# light-meter-A.net
KiCad netlist of a schematic drawn in EAGLE
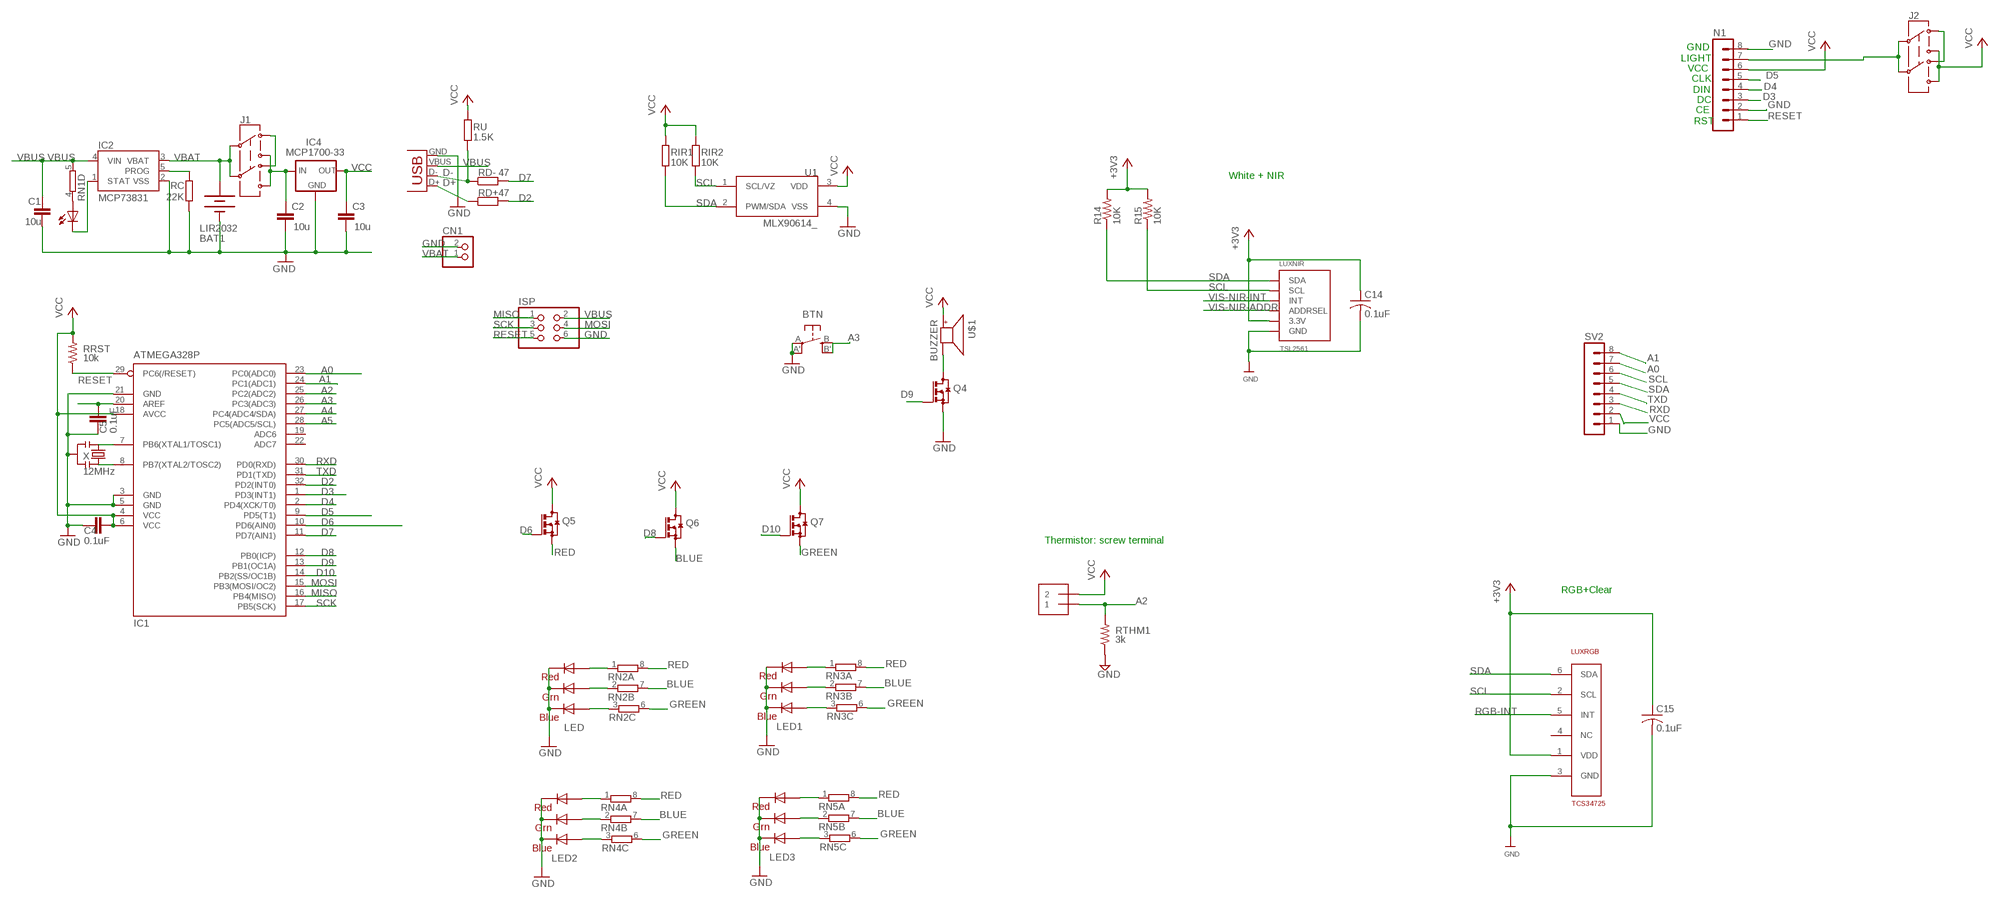
[diagram p0: schematic, sheet 1]

(export (version "E")
  (design (tool "Eeschema 10.0.6"))
  (components
    (comp (ref "BAT1")
      (value "LIR2032")
      (footprint "eagle-import:BATTCOM_20MM_PTH_SMT")
      (libsource (lib "eagle-import") (part "BATTERYBATTCOM_20MM_PTH_SMT"))
    )
    (comp (ref "BTN")
      (value "EVQQ2")
      (footprint "eagle-import:EVQ-Q2")
      (libsource (lib "eagle-import") (part "EVQQ2"))
    )
    (comp (ref "C1")
      (value "10u")
      (footprint "eagle-import:C0805")
      (libsource (lib "eagle-import") (part "resistor_C-EUC0805"))
    )
    (comp (ref "C2")
      (value "10u")
      (footprint "eagle-import:C0805")
      (libsource (lib "eagle-import") (part "resistor_C-EUC0805"))
    )
    (comp (ref "C3")
      (value "10u")
      (footprint "eagle-import:C0805")
      (libsource (lib "eagle-import") (part "resistor_C-EUC0805"))
    )
    (comp (ref "C4")
      (value "0.1uF")
      (footprint "eagle-import:C0805")
      (libsource (lib "eagle-import") (part "C-EUC0805"))
    )
    (comp (ref "C5")
      (value "0.1uF")
      (footprint "eagle-import:C0805")
      (libsource (lib "eagle-import") (part "C-EUC0805"))
    )
    (comp (ref "C14")
      (value "0.1uF")
      (footprint "eagle-import:C0805")
      (libsource (lib "eagle-import") (part "C-USC0805"))
    )
    (comp (ref "C15")
      (value "0.1uF")
      (footprint "eagle-import:C0805")
      (libsource (lib "eagle-import") (part "C-USC0805"))
    )
    (comp (ref "CHG")
      (value "0805")
      (footprint "eagle-import:CHIPLED_0805")
      (libsource (lib "eagle-import") (part "LEDCHIPLED_0805"))
    )
    (comp (ref "CN1")
      (value "JST_2PIN-SMT-RA")
      (footprint "eagle-import:JST-PH-2-SMT-RA")
      (libsource (lib "eagle-import") (part "JST_2PIN-SMT-RA"))
    )
    (comp (ref "IC1")
      (value "ATMEGA328P")
      (footprint "eagle-import:TQFP32-08")
      (fields (field (name "MPN") "ATMEGA8-16AU"))
      (libsource (lib "eagle-import") (part "MEGA8-AI"))
    )
    (comp (ref "IC2")
      (value "MCP73831")
      (footprint "eagle-import:SOT23-5")
      (libsource (lib "eagle-import") (part "MCP73831"))
    )
    (comp (ref "IC4")
      (value "MCP1700-33")
      (footprint "eagle-import:SOT23")
      (libsource (lib "eagle-import") (part "MCP1700SOT233"))
    )
    (comp (ref "ISP")
      (value "PINHD-2X3")
      (footprint "eagle-import:2X03")
      (libsource (lib "eagle-import") (part "PINHD-2X3"))
    )
    (comp (ref "J1")
      (value "AYZ0202")
      (footprint "eagle-import:AYZ0202")
      (libsource (lib "eagle-import") (part "AYZ0202"))
    )
    (comp (ref "J2")
      (value "AYZ0202")
      (footprint "eagle-import:AYZ0202")
      (libsource (lib "eagle-import") (part "AYZ0202"))
    )
    (comp (ref "LED")
      (value "RGBLED5050")
      (footprint "eagle-import:RGBLED5050")
      (libsource (lib "eagle-import") (part "RGBLED5050"))
    )
    (comp (ref "LED1")
      (value "RGBLED5050")
      (footprint "eagle-import:RGBLED5050")
      (libsource (lib "eagle-import") (part "RGBLED5050"))
    )
    (comp (ref "LED2")
      (value "RGBLED5050")
      (footprint "eagle-import:RGBLED5050")
      (libsource (lib "eagle-import") (part "RGBLED5050"))
    )
    (comp (ref "LED3")
      (value "RGBLED5050")
      (footprint "eagle-import:RGBLED5050")
      (libsource (lib "eagle-import") (part "RGBLED5050"))
    )
    (comp (ref "LUXNIR")
      (value "TSL2561")
      (footprint "eagle-import:TSL2561_FN@1")
      (libsource (lib "eagle-import") (part "TSL2561"))
    )
    (comp (ref "LUXRGB")
      (value "TCS34725")
      (footprint "eagle-import:DFN-6")
      (libsource (lib "eagle-import") (part "TCS34725"))
    )
    (comp (ref "N1")
      (value "MA08-1")
      (footprint "eagle-import:MA08-1")
      (libsource (lib "eagle-import") (part "MA08-1"))
    )
    (comp (ref "Q4")
      (value "BSS123")
      (footprint "eagle-import:SOT23")
      (libsource (lib "eagle-import") (part "BSS123"))
    )
    (comp (ref "Q5")
      (value "BSS123")
      (footprint "eagle-import:SOT23")
      (libsource (lib "eagle-import") (part "BSS123"))
    )
    (comp (ref "Q6")
      (value "BSS123")
      (footprint "eagle-import:SOT23")
      (libsource (lib "eagle-import") (part "BSS123"))
    )
    (comp (ref "Q7")
      (value "BSS123")
      (footprint "eagle-import:SOT23")
      (libsource (lib "eagle-import") (part "BSS123"))
    )
    (comp (ref "R14")
      (value "10K")
      (footprint "eagle-import:R0805")
      (libsource (lib "eagle-import") (part "R-US_R0805"))
    )
    (comp (ref "R15")
      (value "10K")
      (footprint "eagle-import:R0805")
      (libsource (lib "eagle-import") (part "R-US_R0805"))
    )
    (comp (ref "RC")
      (value "22K")
      (footprint "eagle-import:R0805")
      (libsource (lib "eagle-import") (part "R-EU_R0805"))
    )
    (comp (ref "RD+")
      (value "47")
      (footprint "eagle-import:R0805")
      (libsource (lib "eagle-import") (part "R-EU_R0805"))
    )
    (comp (ref "RD-")
      (value "47")
      (footprint "eagle-import:R0805")
      (libsource (lib "eagle-import") (part "R-EU_R0805"))
    )
    (comp (ref "RIR1")
      (value "10K")
      (footprint "eagle-import:R0805")
      (libsource (lib "eagle-import") (part "R-EU_R0805"))
    )
    (comp (ref "RIR2")
      (value "10K")
      (footprint "eagle-import:R0805")
      (libsource (lib "eagle-import") (part "R-EU_R0805"))
    )
    (comp (ref "RN1")
      (value "4R-NEXB38V")
      (footprint "eagle-import:EXB38V")
      (libsource (lib "eagle-import") (part "4R-NEXB38V"))
    )
    (comp (ref "RN2")
      (value "4R-NEXB38V")
      (footprint "eagle-import:EXB38V")
      (libsource (lib "eagle-import") (part "4R-NEXB38V"))
    )
    (comp (ref "RN3")
      (value "4R-NEXB38V")
      (footprint "eagle-import:EXB38V")
      (libsource (lib "eagle-import") (part "4R-NEXB38V"))
    )
    (comp (ref "RN4")
      (value "4R-NEXB38V")
      (footprint "eagle-import:EXB38V")
      (libsource (lib "eagle-import") (part "4R-NEXB38V"))
    )
    (comp (ref "RN5")
      (value "4R-NEXB38V")
      (footprint "eagle-import:EXB38V")
      (libsource (lib "eagle-import") (part "4R-NEXB38V"))
    )
    (comp (ref "RRST")
      (value "10k")
      (footprint "eagle-import:R0805@1")
      (libsource (lib "eagle-import") (part "rcl_R-US_R0805"))
    )
    (comp (ref "RTHM1")
      (value "3k")
      (footprint "eagle-import:R0805@1")
      (libsource (lib "eagle-import") (part "rcl_R-US_R0805"))
    )
    (comp (ref "RU")
      (value "1.5K")
      (footprint "eagle-import:R0805")
      (libsource (lib "eagle-import") (part "R-EU_R0805"))
    )
    (comp (ref "SV2")
      (value "MA08-1")
      (footprint "eagle-import:MA08-1")
      (libsource (lib "eagle-import") (part "MA08-1"))
    )
    (comp (ref "THM1")
      (value "1X2-3.5MM")
      (footprint "eagle-import:1X2-3.5MM")
      (libsource (lib "eagle-import") (part "1X2-3.5MM"))
    )
    (comp (ref "U$1")
      (value "BUZZER")
      (footprint "eagle-import:SMT-8585-BUZZER")
      (libsource (lib "eagle-import") (part "BUZZER"))
    )
    (comp (ref "U1")
      (value "MLX90614_")
      (footprint "eagle-import:TO-39")
      (libsource (lib "eagle-import") (part "MLX90614_"))
    )
    (comp (ref "X")
      (value "12MHz")
      (footprint "eagle-import:RESONATOR-SMD")
      (libsource (lib "eagle-import") (part "RESONATORSMD"))
    )
    (comp (ref "X1")
      (value "USBSMD")
      (footprint "eagle-import:USB-MINIB")
      (libsource (lib "eagle-import") (part "USBSMD"))
    )
  )
  (nets
    (net (code "1") (name "+3V3") (class "Default")
      (node (ref "C14") (pin "1") (pinfunction "1_1") (pintype "passive"))
      (node (ref "C15") (pin "1") (pinfunction "1_1") (pintype "passive"))
      (node (ref "LUXNIR") (pin "VDD") (pinfunction "3.3V_VDD") (pintype "bidirectional"))
      (node (ref "LUXRGB") (pin "1") (pinfunction "VDD_1") (pintype "bidirectional"))
      (node (ref "R14") (pin "2") (pinfunction "2_2") (pintype "passive"))
      (node (ref "R15") (pin "2") (pinfunction "2_2") (pintype "passive"))
    )
    (net (code "2") (name "/A0") (class "Default")
      (node (ref "IC1") (pin "23") (pinfunction "PC0(ADC0)_23") (pintype "bidirectional"))
      (node (ref "SV2") (pin "7") (pinfunction "7_7") (pintype "passive"))
    )
    (net (code "3") (name "/A1") (class "Default")
      (node (ref "IC1") (pin "24") (pinfunction "PC1(ADC1)_24") (pintype "bidirectional"))
      (node (ref "SV2") (pin "8") (pinfunction "8_8") (pintype "passive"))
    )
    (net (code "4") (name "/A2") (class "Default")
      (node (ref "IC1") (pin "25") (pinfunction "PC2(ADC2)_25") (pintype "bidirectional"))
      (node (ref "RTHM1") (pin "2") (pinfunction "2_2") (pintype "passive"))
      (node (ref "THM1") (pin "1") (pinfunction "1_1") (pintype "passive"))
    )
    (net (code "5") (name "/A3") (class "Default")
      (node (ref "BTN") (pin "B") (pinfunction "S_B") (pintype "passive"))
      (node (ref "BTN") (pin "B'") (pinfunction "S1_B'") (pintype "passive"))
      (node (ref "IC1") (pin "26") (pinfunction "PC3(ADC3)_26") (pintype "bidirectional"))
    )
    (net (code "6") (name "/A4") (class "Default")
      (node (ref "IC1") (pin "27") (pinfunction "PC4(ADC4/SDA)_27") (pintype "bidirectional"))
    )
    (net (code "7") (name "/A5") (class "Default")
      (node (ref "IC1") (pin "28") (pinfunction "PC5(ADC5/SCL)_28") (pintype "bidirectional"))
    )
    (net (code "8") (name "/BLUE") (class "Default")
      (node (ref "Q6") (pin "2") (pinfunction "S_2") (pintype "passive"))
      (node (ref "RN2") (pin "7") (pinfunction "2_7") (pintype "passive"))
      (node (ref "RN3") (pin "7") (pinfunction "2_7") (pintype "passive"))
      (node (ref "RN4") (pin "7") (pinfunction "2_7") (pintype "passive"))
      (node (ref "RN5") (pin "7") (pinfunction "2_7") (pintype "passive"))
    )
    (net (code "9") (name "/D+") (class "Default")
      (node (ref "RD+") (pin "1") (pinfunction "1_1") (pintype "passive"))
      (node (ref "X1") (pin "D+") (pinfunction "D+_D+") (pintype "bidirectional"))
    )
    (net (code "10") (name "/D-") (class "Default")
      (node (ref "RD-") (pin "1") (pinfunction "1_1") (pintype "passive"))
      (node (ref "RU") (pin "1") (pinfunction "1_1") (pintype "passive"))
      (node (ref "X1") (pin "D-") (pinfunction "D-_D-") (pintype "bidirectional"))
    )
    (net (code "11") (name "/D2") (class "Default")
      (node (ref "IC1") (pin "32") (pinfunction "PD2(INT0)_32") (pintype "bidirectional"))
      (node (ref "RD+") (pin "2") (pinfunction "2_2") (pintype "passive"))
    )
    (net (code "12") (name "/D3") (class "Default")
      (node (ref "IC1") (pin "1") (pinfunction "PD3(INT1)_1") (pintype "bidirectional"))
      (node (ref "N1") (pin "3") (pinfunction "3_3") (pintype "passive"))
    )
    (net (code "13") (name "/D4") (class "Default")
      (node (ref "IC1") (pin "2") (pinfunction "PD4(XCK/T0)_2") (pintype "bidirectional"))
      (node (ref "N1") (pin "4") (pinfunction "4_4") (pintype "passive"))
    )
    (net (code "14") (name "/D5") (class "Default")
      (node (ref "IC1") (pin "9") (pinfunction "PD5(T1)_9") (pintype "bidirectional"))
      (node (ref "N1") (pin "5") (pinfunction "5_5") (pintype "passive"))
    )
    (net (code "15") (name "/D6") (class "Default")
      (node (ref "IC1") (pin "10") (pinfunction "PD6(AIN0)_10") (pintype "bidirectional"))
      (node (ref "Q5") (pin "1") (pinfunction "G_1") (pintype "passive"))
    )
    (net (code "16") (name "/D7") (class "Default")
      (node (ref "IC1") (pin "11") (pinfunction "PD7(AIN1)_11") (pintype "bidirectional"))
      (node (ref "RD-") (pin "2") (pinfunction "2_2") (pintype "passive"))
    )
    (net (code "17") (name "/D8") (class "Default")
      (node (ref "IC1") (pin "12") (pinfunction "PB0(ICP)_12") (pintype "bidirectional"))
      (node (ref "Q6") (pin "1") (pinfunction "G_1") (pintype "passive"))
    )
    (net (code "18") (name "/D9") (class "Default")
      (node (ref "IC1") (pin "13") (pinfunction "PB1(OC1A)_13") (pintype "bidirectional"))
      (node (ref "Q4") (pin "1") (pinfunction "G_1") (pintype "passive"))
    )
    (net (code "19") (name "/D10") (class "Default")
      (node (ref "IC1") (pin "14") (pinfunction "PB2(SS/OC1B)_14") (pintype "bidirectional"))
      (node (ref "Q7") (pin "1") (pinfunction "G_1") (pintype "passive"))
    )
    (net (code "20") (name "/GREEN") (class "Default")
      (node (ref "Q7") (pin "2") (pinfunction "S_2") (pintype "passive"))
      (node (ref "RN2") (pin "6") (pinfunction "2_6") (pintype "passive"))
      (node (ref "RN3") (pin "6") (pinfunction "2_6") (pintype "passive"))
      (node (ref "RN4") (pin "6") (pinfunction "2_6") (pintype "passive"))
      (node (ref "RN5") (pin "6") (pinfunction "2_6") (pintype "passive"))
    )
    (net (code "21") (name "/MISO") (class "Default")
      (node (ref "IC1") (pin "16") (pinfunction "PB4(MISO)_16") (pintype "bidirectional"))
      (node (ref "ISP") (pin "1") (pinfunction "1_1") (pintype "passive"))
    )
    (net (code "22") (name "/MOSI") (class "Default")
      (node (ref "IC1") (pin "15") (pinfunction "PB3(MOSI/OC2)_15") (pintype "bidirectional"))
      (node (ref "ISP") (pin "4") (pinfunction "4_4") (pintype "passive"))
    )
    (net (code "23") (name "/RED") (class "Default")
      (node (ref "Q5") (pin "2") (pinfunction "S_2") (pintype "passive"))
      (node (ref "RN2") (pin "8") (pinfunction "2_8") (pintype "passive"))
      (node (ref "RN3") (pin "8") (pinfunction "2_8") (pintype "passive"))
      (node (ref "RN4") (pin "8") (pinfunction "2_8") (pintype "passive"))
      (node (ref "RN5") (pin "8") (pinfunction "2_8") (pintype "passive"))
    )
    (net (code "24") (name "/RESET") (class "Default")
      (node (ref "IC1") (pin "29") (pinfunction "PC6(/RESET)_29") (pintype "bidirectional"))
      (node (ref "ISP") (pin "5") (pinfunction "5_5") (pintype "passive"))
      (node (ref "N1") (pin "1") (pinfunction "1_1") (pintype "passive"))
      (node (ref "RRST") (pin "1") (pinfunction "1_1") (pintype "passive"))
    )
    (net (code "25") (name "/RGB-INT") (class "Default")
      (node (ref "LUXRGB") (pin "5") (pinfunction "INT_5") (pintype "bidirectional"))
    )
    (net (code "26") (name "/RXD") (class "Default")
      (node (ref "IC1") (pin "30") (pinfunction "PD0(RXD)_30") (pintype "bidirectional"))
      (node (ref "SV2") (pin "3") (pinfunction "3_3") (pintype "passive"))
    )
    (net (code "27") (name "/SCK") (class "Default")
      (node (ref "IC1") (pin "17") (pinfunction "PB5(SCK)_17") (pintype "bidirectional"))
      (node (ref "ISP") (pin "3") (pinfunction "3_3") (pintype "passive"))
    )
    (net (code "28") (name "/SCL") (class "Default")
      (node (ref "LUXNIR") (pin "CLK") (pinfunction "SCL_CLK") (pintype "bidirectional"))
      (node (ref "LUXRGB") (pin "2") (pinfunction "SCL_2") (pintype "bidirectional"))
      (node (ref "R15") (pin "1") (pinfunction "1_1") (pintype "passive"))
      (node (ref "RIR2") (pin "1") (pinfunction "1_1") (pintype "passive"))
      (node (ref "SV2") (pin "6") (pinfunction "6_6") (pintype "passive"))
      (node (ref "U1") (pin "1") (pinfunction "SCL/VZ_1") (pintype "bidirectional"))
    )
    (net (code "29") (name "/SDA") (class "Default")
      (node (ref "LUXNIR") (pin "DATA") (pinfunction "SDA_DATA") (pintype "bidirectional"))
      (node (ref "LUXRGB") (pin "6") (pinfunction "SDA_6") (pintype "bidirectional"))
      (node (ref "R14") (pin "1") (pinfunction "1_1") (pintype "passive"))
      (node (ref "RIR1") (pin "1") (pinfunction "1_1") (pintype "passive"))
      (node (ref "SV2") (pin "5") (pinfunction "5_5") (pintype "passive"))
      (node (ref "U1") (pin "2") (pinfunction "PWM/SDA_2") (pintype "bidirectional"))
    )
    (net (code "30") (name "/TXD") (class "Default")
      (node (ref "IC1") (pin "31") (pinfunction "PD1(TXD)_31") (pintype "bidirectional"))
      (node (ref "SV2") (pin "4") (pinfunction "4_4") (pintype "passive"))
    )
    (net (code "31") (name "/VBAT") (class "Default")
      (node (ref "BAT1") (pin "P$2") (pinfunction "+_P$2") (pintype "power_in"))
      (node (ref "CN1") (pin "1") (pinfunction "2_1") (pintype "passive"))
      (node (ref "IC2") (pin "3") (pinfunction "VBAT_3") (pintype "power_in"))
      (node (ref "J1") (pin "2") (pinfunction "2_2") (pintype "bidirectional"))
      (node (ref "J1") (pin "5") (pinfunction "5_5") (pintype "bidirectional"))
    )
    (net (code "32") (name "/VBUS") (class "Default")
      (node (ref "C1") (pin "1") (pinfunction "1_1") (pintype "passive"))
      (node (ref "IC2") (pin "4") (pinfunction "VIN_4") (pintype "power_in"))
      (node (ref "ISP") (pin "2") (pinfunction "2_2") (pintype "passive"))
      (node (ref "RN1") (pin "5") (pinfunction "2_5") (pintype "passive"))
      (node (ref "X1") (pin "VBUS") (pinfunction "VBUS_VBUS") (pintype "bidirectional"))
    )
    (net (code "33") (name "/VIS-NIR-ADDR") (class "Default")
      (node (ref "LUXNIR") (pin "ADR") (pinfunction "ADDRSEL_ADR") (pintype "bidirectional"))
    )
    (net (code "34") (name "/VIS-NIR-INT") (class "Default")
      (node (ref "LUXNIR") (pin "INT") (pinfunction "INT_INT") (pintype "bidirectional"))
    )
    (net (code "35") (name "GND") (class "Default")
      (node (ref "BAT1") (pin "P$1") (pinfunction "-_P$1") (pintype "power_in"))
      (node (ref "BTN") (pin "A") (pinfunction "P_A") (pintype "passive"))
      (node (ref "BTN") (pin "A'") (pinfunction "P1_A'") (pintype "passive"))
      (node (ref "C1") (pin "2") (pinfunction "2_2") (pintype "passive"))
      (node (ref "C14") (pin "2") (pinfunction "2_2") (pintype "passive"))
      (node (ref "C15") (pin "2") (pinfunction "2_2") (pintype "passive"))
      (node (ref "C2") (pin "2") (pinfunction "2_2") (pintype "passive"))
      (node (ref "C3") (pin "2") (pinfunction "2_2") (pintype "passive"))
      (node (ref "C4") (pin "1") (pinfunction "1_1") (pintype "passive"))
      (node (ref "C5") (pin "1") (pinfunction "1_1") (pintype "passive"))
      (node (ref "CN1") (pin "2") (pinfunction "1_2") (pintype "passive"))
      (node (ref "IC1") (pin "21") (pinfunction "GND_21") (pintype "power_in"))
      (node (ref "IC1") (pin "3") (pinfunction "GND_3") (pintype "power_in"))
      (node (ref "IC1") (pin "5") (pinfunction "GND_5") (pintype "power_in"))
      (node (ref "IC2") (pin "2") (pinfunction "VSS_2") (pintype "power_in"))
      (node (ref "IC4") (pin "1") (pinfunction "GND_1") (pintype "input"))
      (node (ref "ISP") (pin "6") (pinfunction "6_6") (pintype "passive"))
      (node (ref "LED") (pin "4") (pinfunction "BLUE_C_4") (pintype "bidirectional"))
      (node (ref "LED") (pin "5") (pinfunction "RED_C_5") (pintype "bidirectional"))
      (node (ref "LED") (pin "6") (pinfunction "GREEN_C_6") (pintype "bidirectional"))
      (node (ref "LED1") (pin "4") (pinfunction "BLUE_C_4") (pintype "bidirectional"))
      (node (ref "LED1") (pin "5") (pinfunction "RED_C_5") (pintype "bidirectional"))
      (node (ref "LED1") (pin "6") (pinfunction "GREEN_C_6") (pintype "bidirectional"))
      (node (ref "LED2") (pin "4") (pinfunction "BLUE_C_4") (pintype "bidirectional"))
      (node (ref "LED2") (pin "5") (pinfunction "RED_C_5") (pintype "bidirectional"))
      (node (ref "LED2") (pin "6") (pinfunction "GREEN_C_6") (pintype "bidirectional"))
      (node (ref "LED3") (pin "4") (pinfunction "BLUE_C_4") (pintype "bidirectional"))
      (node (ref "LED3") (pin "5") (pinfunction "RED_C_5") (pintype "bidirectional"))
      (node (ref "LED3") (pin "6") (pinfunction "GREEN_C_6") (pintype "bidirectional"))
      (node (ref "LUXNIR") (pin "VSS") (pinfunction "GND_VSS") (pintype "bidirectional"))
      (node (ref "LUXRGB") (pin "3") (pinfunction "GND_3") (pintype "bidirectional"))
      (node (ref "N1") (pin "2") (pinfunction "2_2") (pintype "passive"))
      (node (ref "N1") (pin "8") (pinfunction "8_8") (pintype "passive"))
      (node (ref "Q4") (pin "2") (pinfunction "S_2") (pintype "passive"))
      (node (ref "RC") (pin "1") (pinfunction "1_1") (pintype "passive"))
      (node (ref "RTHM1") (pin "1") (pinfunction "1_1") (pintype "passive"))
      (node (ref "SV2") (pin "1") (pinfunction "1_1") (pintype "passive"))
      (node (ref "U1") (pin "4") (pinfunction "VSS_4") (pintype "bidirectional"))
      (node (ref "X") (pin "2") (pinfunction "2_2") (pintype "passive"))
      (node (ref "X1") (pin "GND") (pinfunction "GND_GND") (pintype "bidirectional"))
    )
    (net (code "36") (name "Net-(IC1-AREF)") (class "Default")
      (node (ref "C5") (pin "2") (pinfunction "2_2") (pintype "passive"))
      (node (ref "IC1") (pin "20") (pinfunction "AREF_20") (pintype "passive"))
    )
    (net (code "37") (name "Net-(IC1-PB6(XTAL1{slash}TOSC1))") (class "Default")
      (node (ref "IC1") (pin "7") (pinfunction "PB6(XTAL1/TOSC1)_7") (pintype "bidirectional"))
      (node (ref "X") (pin "1") (pinfunction "1_1") (pintype "passive"))
    )
    (net (code "38") (name "Net-(IC1-PB7(XTAL2{slash}TOSC2))") (class "Default")
      (node (ref "IC1") (pin "8") (pinfunction "PB7(XTAL2/TOSC2)_8") (pintype "bidirectional"))
      (node (ref "X") (pin "3") (pinfunction "3_3") (pintype "passive"))
    )
    (net (code "39") (name "Net-(IC2-PROG)") (class "Default")
      (node (ref "IC2") (pin "5") (pinfunction "PROG_5") (pintype "input"))
      (node (ref "RC") (pin "2") (pinfunction "2_2") (pintype "passive"))
    )
    (net (code "40") (name "Net-(IC2-STAT)") (class "Default")
      (node (ref "CHG") (pin "C") (pinfunction "C_C") (pintype "passive"))
      (node (ref "IC2") (pin "1") (pinfunction "STAT_1") (pintype "output"))
    )
    (net (code "41") (name "Net-(IC4-IN)") (class "Default")
      (node (ref "C2") (pin "1") (pinfunction "1_1") (pintype "passive"))
      (node (ref "IC4") (pin "3") (pinfunction "IN_3") (pintype "input"))
      (node (ref "J1") (pin "1") (pinfunction "3_1") (pintype "bidirectional"))
      (node (ref "J1") (pin "4") (pinfunction "6_4") (pintype "bidirectional"))
    )
    (net (code "42") (name "Net-(J1-1)") (class "Default")
      (node (ref "J1") (pin "3") (pinfunction "1_3") (pintype "bidirectional"))
      (node (ref "J1") (pin "6") (pinfunction "4_6") (pintype "bidirectional"))
    )
    (net (code "43") (name "Net-(J2-1)") (class "Default")
      (node (ref "J2") (pin "3") (pinfunction "1_3") (pintype "bidirectional"))
      (node (ref "J2") (pin "6") (pinfunction "4_6") (pintype "bidirectional"))
    )
    (net (code "44") (name "Net-(J2-Pad2)") (class "Default")
      (node (ref "J2") (pin "2") (pinfunction "2_2") (pintype "bidirectional"))
      (node (ref "J2") (pin "5") (pinfunction "5_5") (pintype "bidirectional"))
      (node (ref "N1") (pin "7") (pinfunction "7_7") (pintype "passive"))
    )
    (net (code "45") (name "Net-(LED-BLUE_A)") (class "Default")
      (node (ref "LED") (pin "3") (pinfunction "BLUE_A_3") (pintype "bidirectional"))
      (node (ref "RN2") (pin "3") (pinfunction "1_3") (pintype "passive"))
    )
    (net (code "46") (name "Net-(LED-GREEN_A)") (class "Default")
      (node (ref "LED") (pin "1") (pinfunction "GREEN_A_1") (pintype "bidirectional"))
      (node (ref "RN2") (pin "2") (pinfunction "1_2") (pintype "passive"))
    )
    (net (code "47") (name "Net-(LED-RED_A)") (class "Default")
      (node (ref "LED") (pin "2") (pinfunction "RED_A_2") (pintype "bidirectional"))
      (node (ref "RN2") (pin "1") (pinfunction "1_1") (pintype "passive"))
    )
    (net (code "48") (name "Net-(LED1-BLUE_A)") (class "Default")
      (node (ref "LED1") (pin "3") (pinfunction "BLUE_A_3") (pintype "bidirectional"))
      (node (ref "RN3") (pin "3") (pinfunction "1_3") (pintype "passive"))
    )
    (net (code "49") (name "Net-(LED1-GREEN_A)") (class "Default")
      (node (ref "LED1") (pin "1") (pinfunction "GREEN_A_1") (pintype "bidirectional"))
      (node (ref "RN3") (pin "2") (pinfunction "1_2") (pintype "passive"))
    )
    (net (code "50") (name "Net-(LED1-RED_A)") (class "Default")
      (node (ref "LED1") (pin "2") (pinfunction "RED_A_2") (pintype "bidirectional"))
      (node (ref "RN3") (pin "1") (pinfunction "1_1") (pintype "passive"))
    )
    (net (code "51") (name "Net-(LED2-BLUE_A)") (class "Default")
      (node (ref "LED2") (pin "3") (pinfunction "BLUE_A_3") (pintype "bidirectional"))
      (node (ref "RN4") (pin "3") (pinfunction "1_3") (pintype "passive"))
    )
    (net (code "52") (name "Net-(LED2-GREEN_A)") (class "Default")
      (node (ref "LED2") (pin "1") (pinfunction "GREEN_A_1") (pintype "bidirectional"))
      (node (ref "RN4") (pin "2") (pinfunction "1_2") (pintype "passive"))
    )
    (net (code "53") (name "Net-(LED2-RED_A)") (class "Default")
      (node (ref "LED2") (pin "2") (pinfunction "RED_A_2") (pintype "bidirectional"))
      (node (ref "RN4") (pin "1") (pinfunction "1_1") (pintype "passive"))
    )
    (net (code "54") (name "Net-(LED3-BLUE_A)") (class "Default")
      (node (ref "LED3") (pin "3") (pinfunction "BLUE_A_3") (pintype "bidirectional"))
      (node (ref "RN5") (pin "3") (pinfunction "1_3") (pintype "passive"))
    )
    (net (code "55") (name "Net-(LED3-GREEN_A)") (class "Default")
      (node (ref "LED3") (pin "1") (pinfunction "GREEN_A_1") (pintype "bidirectional"))
      (node (ref "RN5") (pin "2") (pinfunction "1_2") (pintype "passive"))
    )
    (net (code "56") (name "Net-(LED3-RED_A)") (class "Default")
      (node (ref "LED3") (pin "2") (pinfunction "RED_A_2") (pintype "bidirectional"))
      (node (ref "RN5") (pin "1") (pinfunction "1_1") (pintype "passive"))
    )
    (net (code "57") (name "Net-(Q4-D)") (class "Default")
      (node (ref "Q4") (pin "3") (pinfunction "D_3") (pintype "passive"))
      (node (ref "U$1") (pin "-") (pinfunction "-_-") (pintype "passive"))
    )
    (net (code "58") (name "Net-(RN1D-1)") (class "Default")
      (node (ref "CHG") (pin "A") (pinfunction "A_A") (pintype "passive"))
      (node (ref "RN1") (pin "4") (pinfunction "1_4") (pintype "passive"))
    )
    (net (code "59") (name "VCC") (class "Default")
      (node (ref "C3") (pin "1") (pinfunction "1_1") (pintype "passive"))
      (node (ref "C4") (pin "2") (pinfunction "2_2") (pintype "passive"))
      (node (ref "IC1") (pin "18") (pinfunction "AVCC_18") (pintype "power_in"))
      (node (ref "IC1") (pin "4") (pinfunction "VCC_4") (pintype "power_in"))
      (node (ref "IC1") (pin "6") (pinfunction "VCC_6") (pintype "power_in"))
      (node (ref "IC4") (pin "2") (pinfunction "OUT_2") (pintype "passive"))
      (node (ref "J2") (pin "1") (pinfunction "3_1") (pintype "bidirectional"))
      (node (ref "J2") (pin "4") (pinfunction "6_4") (pintype "bidirectional"))
      (node (ref "N1") (pin "6") (pinfunction "6_6") (pintype "passive"))
      (node (ref "Q5") (pin "3") (pinfunction "D_3") (pintype "passive"))
      (node (ref "Q6") (pin "3") (pinfunction "D_3") (pintype "passive"))
      (node (ref "Q7") (pin "3") (pinfunction "D_3") (pintype "passive"))
      (node (ref "RIR1") (pin "2") (pinfunction "2_2") (pintype "passive"))
      (node (ref "RIR2") (pin "2") (pinfunction "2_2") (pintype "passive"))
      (node (ref "RRST") (pin "2") (pinfunction "2_2") (pintype "passive"))
      (node (ref "RU") (pin "2") (pinfunction "2_2") (pintype "passive"))
      (node (ref "SV2") (pin "2") (pinfunction "2_2") (pintype "passive"))
      (node (ref "THM1") (pin "2") (pinfunction "2_2") (pintype "passive"))
      (node (ref "U$1") (pin "+") (pinfunction "+_+") (pintype "passive"))
      (node (ref "U1") (pin "3") (pinfunction "VDD_3") (pintype "bidirectional"))
    )
    (net (code "60") (name "unconnected-(IC1-ADC6-Pad19)") (class "Default")
      (node (ref "IC1") (pin "19") (pinfunction "ADC6_19") (pintype "bidirectional"))
    )
    (net (code "61") (name "unconnected-(IC1-ADC7-Pad22)") (class "Default")
      (node (ref "IC1") (pin "22") (pinfunction "ADC7_22") (pintype "bidirectional"))
    )
    (net (code "62") (name "unconnected-(LUXRGB-NC-Pad4)") (class "Default")
      (node (ref "LUXRGB") (pin "4") (pinfunction "NC_4") (pintype "bidirectional"))
    )
  )
)
